# 4_STM32.net
KiCad netlist of a schematic drawn in Altium Designer
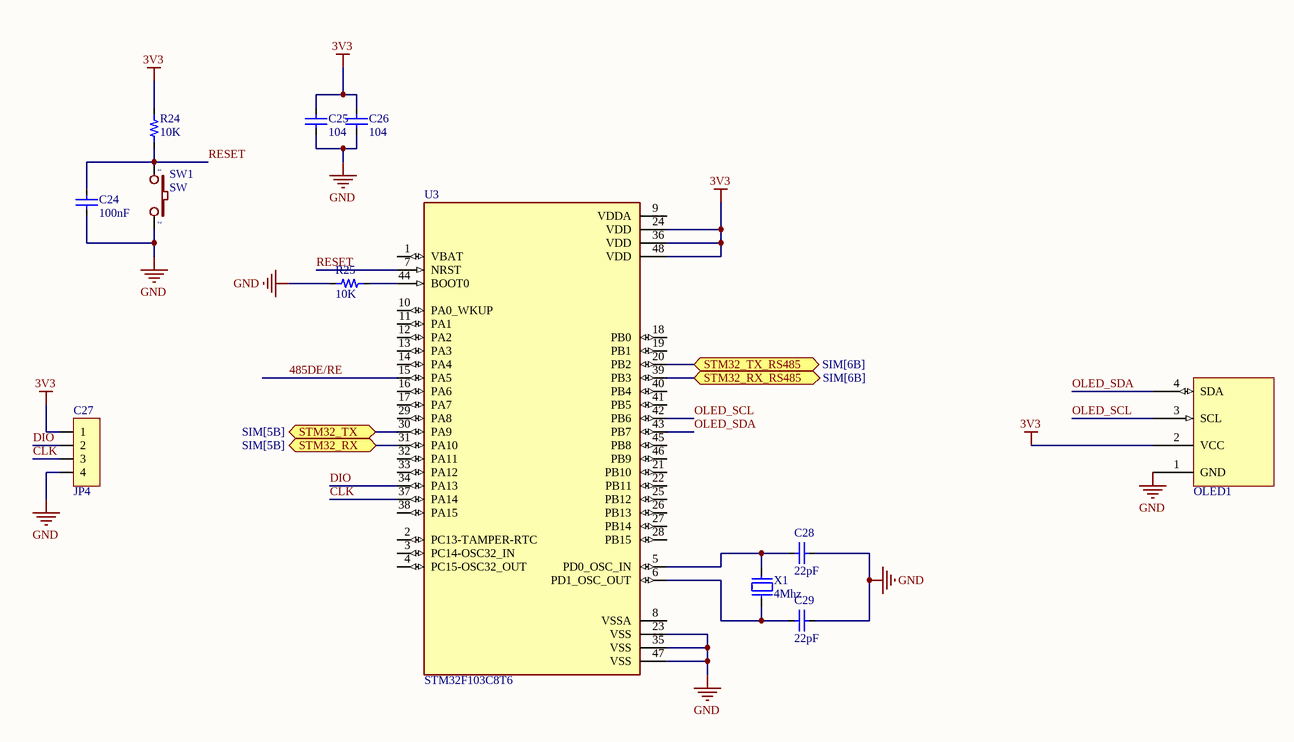
[diagram p0: 4.STM32.SchDoc]

(export (version "E")
  (design (tool "Eeschema 10.0.6"))
  (components
    (comp (ref "C24")
      (value "100nF")
      (footprint "CAP_0805")
      (description "Capacitor")
      (fields (field (name "PUBLISHER") "Altium Limited"))
      (libsource (lib "My-Library") (part "CapSMD"))
    )
    (comp (ref "C25")
      (value "104")
      (footprint "CAP_0805")
      (description "Capacitor")
      (fields (field (name "PUBLISHER") "Altium Limited"))
      (libsource (lib "My-Library") (part "CapSMD"))
    )
    (comp (ref "C26")
      (value "104")
      (footprint "CAP_0805")
      (description "Capacitor")
      (fields (field (name "PUBLISHER") "Altium Limited"))
      (libsource (lib "My-Library") (part "CapSMD"))
    )
    (comp (ref "C27")
      (value "JP4")
      (footprint "JP4-C1T")
      (description "WR-PHD 2.54 mm Angled Socket Header")
      (fields
        (field (name "MANUFACTURER") "Würth Elektronik eiSos GmbH")
        (field (name "PARTNO") "613004143121")
        (field (name "CREATED BY") "Karrer Zheng")
      )
      (libsource (lib "My-Library") (part "JP4"))
    )
    (comp (ref "C28")
      (value "22pF")
      (footprint "CAP_0805")
      (description "Capacitor")
      (fields (field (name "PUBLISHER") "Altium Limited"))
      (libsource (lib "My-Library") (part "CapSMD"))
    )
    (comp (ref "C29")
      (value "22pF")
      (footprint "CAP_0805")
      (description "Capacitor")
      (fields (field (name "PUBLISHER") "Altium Limited"))
      (libsource (lib "My-Library") (part "CapSMD"))
    )
    (comp (ref "OLED1")
      (value "SSD1306")
      (footprint "OLED 1.3")
      (description "OLED 1.3\" SSD1306")
      (libsource (lib "My-Library") (part "OLED 1.3{dblquote}"))
    )
    (comp (ref "R24")
      (value "10K")
      (footprint "RES-SMD-0101")
      (description "Resistor")
      (fields
        (field (name "MANUFACTURER") "Generic Components")
        (field (name "PUBLISHER") "Altium Hobart Technology Centre")
      )
      (libsource (lib "My-Library") (part "Resistor - SMD"))
    )
    (comp (ref "R25")
      (value "10K")
      (footprint "RES-SMD-0101")
      (description "Resistor")
      (fields
        (field (name "MANUFACTURER") "Generic Components")
        (field (name "PUBLISHER") "Altium Hobart Technology Centre")
      )
      (libsource (lib "My-Library") (part "Resistor - SMD"))
    )
    (comp (ref "SW1")
      (value "SW")
      (footprint "SW2")
      (description "Switch button 2 pin")
      (libsource (lib "My-Library") (part "SW2"))
    )
    (comp (ref "U3")
      (value "STM32F103C8T6")
      (footprint "STM32F103C8T6")
      (libsource (lib "My-Library") (part "STM32F103C8T6"))
    )
    (comp (ref "X1")
      (value "4Mhz")
      (footprint "XT2")
      (description "Crystal For all Crystal 2pin.")
      (libsource (lib "My-Library") (part "XT2"))
    )
  )
  (nets
    (net (code "1") (name "/485DE{slash}RE") (class "Default")
      (node (ref "U3") (pin "15") (pinfunction "PA5_15") (pintype "bidirectional"))
    )
    (net (code "2") (name "/CLK") (class "Default")
      (node (ref "C27") (pin "3") (pinfunction "3_3") (pintype "passive"))
      (node (ref "U3") (pin "37") (pinfunction "PA14_37") (pintype "bidirectional"))
    )
    (net (code "3") (name "/DIO") (class "Default")
      (node (ref "C27") (pin "2") (pinfunction "2_2") (pintype "passive"))
      (node (ref "U3") (pin "34") (pinfunction "PA13_34") (pintype "bidirectional"))
    )
    (net (code "4") (name "/OLED_SCL") (class "Default")
      (node (ref "OLED1") (pin "3") (pinfunction "SCL_3") (pintype "input"))
      (node (ref "U3") (pin "42") (pinfunction "PB6_42") (pintype "bidirectional"))
    )
    (net (code "5") (name "/OLED_SDA") (class "Default")
      (node (ref "OLED1") (pin "4") (pinfunction "SDA_4") (pintype "bidirectional"))
      (node (ref "U3") (pin "43") (pinfunction "PB7_43") (pintype "bidirectional"))
    )
    (net (code "6") (name "/RESET") (class "Default")
      (node (ref "C24") (pin "1") (pinfunction "1_1") (pintype "passive"))
      (node (ref "R24") (pin "2") (pinfunction "2_2") (pintype "passive"))
      (node (ref "SW1") (pin "1") (pinfunction "1_1") (pintype "passive"))
      (node (ref "U3") (pin "7") (pinfunction "NRST_7") (pintype "input"))
    )
    (net (code "7") (name "/STM32_RX") (class "Default")
      (node (ref "U3") (pin "31") (pinfunction "PA10_31") (pintype "bidirectional"))
    )
    (net (code "8") (name "/STM32_RX_RS485") (class "Default")
      (node (ref "U3") (pin "39") (pinfunction "PB3_39") (pintype "bidirectional"))
    )
    (net (code "9") (name "/STM32_TX") (class "Default")
      (node (ref "U3") (pin "30") (pinfunction "PA9_30") (pintype "bidirectional"))
    )
    (net (code "10") (name "/STM32_TX_RS485") (class "Default")
      (node (ref "U3") (pin "20") (pinfunction "PB2_20") (pintype "bidirectional"))
    )
    (net (code "11") (name "3V3") (class "Default")
      (node (ref "C25") (pin "1") (pinfunction "1_1") (pintype "passive"))
      (node (ref "C26") (pin "1") (pinfunction "1_1") (pintype "passive"))
      (node (ref "C27") (pin "1") (pinfunction "1_1") (pintype "passive"))
      (node (ref "OLED1") (pin "2") (pinfunction "VCC_2") (pintype "power_in"))
      (node (ref "R24") (pin "1") (pinfunction "1_1") (pintype "passive"))
      (node (ref "U3") (pin "24") (pinfunction "VDD_24") (pintype "power_in"))
      (node (ref "U3") (pin "36") (pinfunction "VDD_36") (pintype "power_in"))
      (node (ref "U3") (pin "48") (pinfunction "VDD_48") (pintype "power_in"))
    )
    (net (code "12") (name "GND") (class "Default")
      (node (ref "C24") (pin "2") (pinfunction "2_2") (pintype "passive"))
      (node (ref "C25") (pin "2") (pinfunction "2_2") (pintype "passive"))
      (node (ref "C26") (pin "2") (pinfunction "2_2") (pintype "passive"))
      (node (ref "C27") (pin "4") (pinfunction "4_4") (pintype "passive"))
      (node (ref "C28") (pin "1") (pinfunction "1_1") (pintype "passive"))
      (node (ref "C29") (pin "1") (pinfunction "1_1") (pintype "passive"))
      (node (ref "OLED1") (pin "1") (pinfunction "GND_1") (pintype "power_in"))
      (node (ref "R25") (pin "1") (pinfunction "1_1") (pintype "passive"))
      (node (ref "SW1") (pin "2") (pinfunction "2_2") (pintype "passive"))
      (node (ref "U3") (pin "23") (pinfunction "VSS_23") (pintype "power_in"))
      (node (ref "U3") (pin "35") (pinfunction "VSS_35") (pintype "power_in"))
      (node (ref "U3") (pin "47") (pinfunction "VSS_47") (pintype "power_in"))
    )
    (net (code "13") (name "Net-(U3-BOOT0)") (class "Default")
      (node (ref "R25") (pin "2") (pinfunction "2_2") (pintype "passive"))
      (node (ref "U3") (pin "44") (pinfunction "BOOT0_44") (pintype "input"))
    )
    (net (code "14") (name "Net-(U3-PD0_OSC_IN)") (class "Default")
      (node (ref "C28") (pin "2") (pinfunction "2_2") (pintype "passive"))
      (node (ref "U3") (pin "5") (pinfunction "PD0_OSC_IN_5") (pintype "bidirectional"))
      (node (ref "X1") (pin "2") (pinfunction "2_2") (pintype "passive"))
    )
    (net (code "15") (name "Net-(U3-PD1_OSC_OUT)") (class "Default")
      (node (ref "C29") (pin "2") (pinfunction "2_2") (pintype "passive"))
      (node (ref "U3") (pin "6") (pinfunction "PD1_OSC_OUT_6") (pintype "bidirectional"))
      (node (ref "X1") (pin "1") (pinfunction "1_1") (pintype "passive"))
    )
    (net (code "16") (name "unconnected-(U3-PA0_WKUP-Pad10)") (class "Default")
      (node (ref "U3") (pin "10") (pinfunction "PA0_WKUP_10") (pintype "bidirectional"))
    )
    (net (code "17") (name "unconnected-(U3-PA1-Pad11)") (class "Default")
      (node (ref "U3") (pin "11") (pinfunction "PA1_11") (pintype "bidirectional"))
    )
    (net (code "18") (name "unconnected-(U3-PA2-Pad12)") (class "Default")
      (node (ref "U3") (pin "12") (pinfunction "PA2_12") (pintype "bidirectional"))
    )
    (net (code "19") (name "unconnected-(U3-PA3-Pad13)") (class "Default")
      (node (ref "U3") (pin "13") (pinfunction "PA3_13") (pintype "bidirectional"))
    )
    (net (code "20") (name "unconnected-(U3-PA4-Pad14)") (class "Default")
      (node (ref "U3") (pin "14") (pinfunction "PA4_14") (pintype "bidirectional"))
    )
    (net (code "21") (name "unconnected-(U3-PA6-Pad16)") (class "Default")
      (node (ref "U3") (pin "16") (pinfunction "PA6_16") (pintype "bidirectional"))
    )
    (net (code "22") (name "unconnected-(U3-PA7-Pad17)") (class "Default")
      (node (ref "U3") (pin "17") (pinfunction "PA7_17") (pintype "bidirectional"))
    )
    (net (code "23") (name "unconnected-(U3-PA8-Pad29)") (class "Default")
      (node (ref "U3") (pin "29") (pinfunction "PA8_29") (pintype "bidirectional"))
    )
    (net (code "24") (name "unconnected-(U3-PA11-Pad32)") (class "Default")
      (node (ref "U3") (pin "32") (pinfunction "PA11_32") (pintype "bidirectional"))
    )
    (net (code "25") (name "unconnected-(U3-PA12-Pad33)") (class "Default")
      (node (ref "U3") (pin "33") (pinfunction "PA12_33") (pintype "bidirectional"))
    )
    (net (code "26") (name "unconnected-(U3-PA15-Pad38)") (class "Default")
      (node (ref "U3") (pin "38") (pinfunction "PA15_38") (pintype "bidirectional"))
    )
    (net (code "27") (name "unconnected-(U3-PB0-Pad18)") (class "Default")
      (node (ref "U3") (pin "18") (pinfunction "PB0_18") (pintype "bidirectional"))
    )
    (net (code "28") (name "unconnected-(U3-PB1-Pad19)") (class "Default")
      (node (ref "U3") (pin "19") (pinfunction "PB1_19") (pintype "bidirectional"))
    )
    (net (code "29") (name "unconnected-(U3-PB4-Pad40)") (class "Default")
      (node (ref "U3") (pin "40") (pinfunction "PB4_40") (pintype "bidirectional"))
    )
    (net (code "30") (name "unconnected-(U3-PB5-Pad41)") (class "Default")
      (node (ref "U3") (pin "41") (pinfunction "PB5_41") (pintype "bidirectional"))
    )
    (net (code "31") (name "unconnected-(U3-PB8-Pad45)") (class "Default")
      (node (ref "U3") (pin "45") (pinfunction "PB8_45") (pintype "bidirectional"))
    )
    (net (code "32") (name "unconnected-(U3-PB9-Pad46)") (class "Default")
      (node (ref "U3") (pin "46") (pinfunction "PB9_46") (pintype "bidirectional"))
    )
    (net (code "33") (name "unconnected-(U3-PB10-Pad21)") (class "Default")
      (node (ref "U3") (pin "21") (pinfunction "PB10_21") (pintype "bidirectional"))
    )
    (net (code "34") (name "unconnected-(U3-PB11-Pad22)") (class "Default")
      (node (ref "U3") (pin "22") (pinfunction "PB11_22") (pintype "bidirectional"))
    )
    (net (code "35") (name "unconnected-(U3-PB12-Pad25)") (class "Default")
      (node (ref "U3") (pin "25") (pinfunction "PB12_25") (pintype "bidirectional"))
    )
    (net (code "36") (name "unconnected-(U3-PB13-Pad26)") (class "Default")
      (node (ref "U3") (pin "26") (pinfunction "PB13_26") (pintype "bidirectional"))
    )
    (net (code "37") (name "unconnected-(U3-PB14-Pad27)") (class "Default")
      (node (ref "U3") (pin "27") (pinfunction "PB14_27") (pintype "bidirectional"))
    )
    (net (code "38") (name "unconnected-(U3-PB15-Pad28)") (class "Default")
      (node (ref "U3") (pin "28") (pinfunction "PB15_28") (pintype "bidirectional"))
    )
    (net (code "39") (name "unconnected-(U3-PC13-TAMPER-RTC-Pad2)") (class "Default")
      (node (ref "U3") (pin "2") (pinfunction "PC13-TAMPER-RTC_2") (pintype "bidirectional"))
    )
    (net (code "40") (name "unconnected-(U3-PC14-OSC32_IN-Pad3)") (class "Default")
      (node (ref "U3") (pin "3") (pinfunction "PC14-OSC32_IN_3") (pintype "bidirectional"))
    )
    (net (code "41") (name "unconnected-(U3-PC15-OSC32_OUT-Pad4)") (class "Default")
      (node (ref "U3") (pin "4") (pinfunction "PC15-OSC32_OUT_4") (pintype "bidirectional"))
    )
    (net (code "42") (name "unconnected-(U3-VBAT-Pad1)") (class "Default")
      (node (ref "U3") (pin "1") (pinfunction "VBAT_1") (pintype "bidirectional"))
    )
    (net (code "43") (name "unconnected-(U3-VDDA-Pad9)") (class "Default")
      (node (ref "U3") (pin "9") (pinfunction "VDDA_9") (pintype "power_in"))
    )
    (net (code "44") (name "unconnected-(U3-VSSA-Pad8)") (class "Default")
      (node (ref "U3") (pin "8") (pinfunction "VSSA_8") (pintype "power_in"))
    )
  )
)
